# VFC.net
KiCad netlist of a schematic drawn in Altium Designer
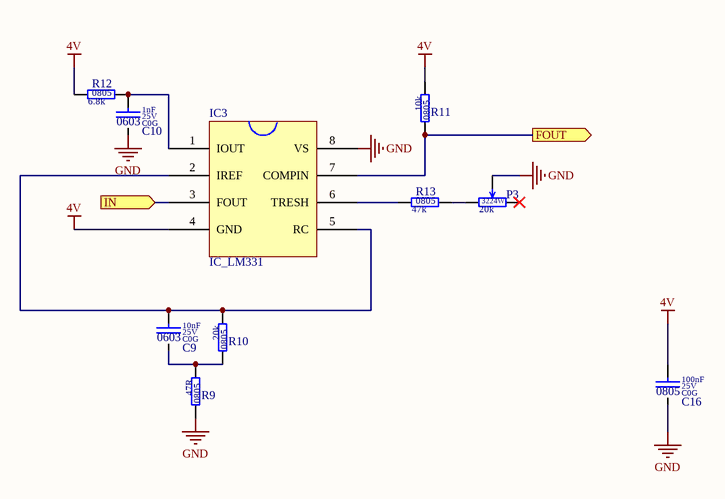
[diagram p0: VFC.SchDoc]

(export (version "E")
  (design (tool "Eeschema 10.0.6"))
  (components
    (comp (ref "C9")
      (value "10nF")
      (footprint "C_0603_1608")
      (description "Capacitor")
      (fields
        (field (name "DIELECTRIC") "C0G")
        (field (name "VOLTAGE") "25V")
        (field (name "SCH_FOOTPRINT") "0603")
        (field (name "Comment") "C_10nF_0603_C0G_25V_5")
      )
      (libsource (lib "SIUE_Symbol") (part "C_10nF_0603_C0G_25V_5"))
    )
    (comp (ref "C10")
      (value "1nF")
      (footprint "C_0603_1608")
      (description "Capacitor")
      (fields
        (field (name "DIELECTRIC") "C0G")
        (field (name "VOLTAGE") "25V")
        (field (name "SCH_FOOTPRINT") "0603")
        (field (name "Comment") "C_1nF_0603_C0G_25V_5")
      )
      (libsource (lib "SIUE_Symbol") (part "C_1nF_0603_C0G_25V_5"))
    )
    (comp (ref "C16")
      (value "100nF")
      (footprint "C_0805_2012")
      (description "Capacitor")
      (fields
        (field (name "DIELECTRIC") "C0G")
        (field (name "VOLTAGE") "25V")
        (field (name "SCH_FOOTPRINT") "0805")
        (field (name "Comment") "C_100nF_0805_C0G_25V_5")
      )
      (libsource (lib "SIUE_Symbol") (part "C_100nF_0805_C0G_25V_5"))
    )
    (comp (ref "IC3") (value "IC_LM331") (footprint "DIP8") (libsource (lib "SIUE_Symbol") (part "IC_LM331")))
    (comp (ref "P3")
      (value "20k")
      (footprint "Potentiometer")
      (fields (field (name "SCH_FOOTPRINT") "3224W") (field (name "Comment") "POT"))
      (libsource (lib "SIUE_Symbol") (part "POT"))
    )
    (comp (ref "R9")
      (value "R_47R_0805_5")
      (footprint "R_0805_2012")
      (fields
        (field (name "TOLERANCE") "5")
        (field (name "SCH_FOOTPRINT") "0805")
        (field (name "RESISTANCE") "47R")
      )
      (libsource (lib "SIUE_Symbol") (part "R_47R_0805_5"))
    )
    (comp (ref "R10")
      (value "R_22k_0805_5")
      (footprint "R_0805_2012")
      (fields
        (field (name "TOLERANCE") "5")
        (field (name "SCH_FOOTPRINT") "0805")
        (field (name "RESISTANCE") "20k")
      )
      (libsource (lib "SIUE_Symbol") (part "R_22k_0805_5"))
    )
    (comp (ref "R11")
      (value "R_10k_0805_5")
      (footprint "R_0805_2012")
      (fields
        (field (name "TOLERANCE") "5")
        (field (name "SCH_FOOTPRINT") "0805")
        (field (name "RESISTANCE") "10k")
      )
      (libsource (lib "SIUE_Symbol") (part "R_10k_0805_5"))
    )
    (comp (ref "R12")
      (value "R_6.8k_0805_5")
      (footprint "R_0805_2012")
      (fields
        (field (name "TOLERANCE") "5")
        (field (name "SCH_FOOTPRINT") "0805")
        (field (name "RESISTANCE") "6.8k")
      )
      (libsource (lib "SIUE_Symbol") (part "R_6.8k_0805_5"))
    )
    (comp (ref "R13")
      (value "R_47k_0805_5")
      (footprint "R_0805_2012")
      (fields
        (field (name "TOLERANCE") "5")
        (field (name "SCH_FOOTPRINT") "0805")
        (field (name "RESISTANCE") "47k")
      )
      (libsource (lib "SIUE_Symbol") (part "R_47k_0805_5"))
    )
  )
  (nets
    (net (code "1") (name "/FOUT") (class "Default")
      (node (ref "IC3") (pin "7") (pinfunction "COMPIN_7") (pintype "passive"))
      (node (ref "R11") (pin "2") (pinfunction "2_2") (pintype "passive"))
    )
    (net (code "2") (name "/IN") (class "Default")
      (node (ref "IC3") (pin "3") (pinfunction "FOUT_3") (pintype "passive"))
    )
    (net (code "3") (name "4V") (class "Default")
      (node (ref "C16") (pin "1") (pinfunction "1_1") (pintype "passive"))
      (node (ref "IC3") (pin "4") (pinfunction "GND_4") (pintype "passive"))
      (node (ref "R11") (pin "1") (pinfunction "1_1") (pintype "passive"))
      (node (ref "R12") (pin "1") (pinfunction "1_1") (pintype "passive"))
    )
    (net (code "4") (name "GND") (class "Default")
      (node (ref "C10") (pin "2") (pinfunction "2_2") (pintype "passive"))
      (node (ref "C16") (pin "2") (pinfunction "2_2") (pintype "passive"))
      (node (ref "IC3") (pin "8") (pinfunction "VS_8") (pintype "passive"))
      (node (ref "P3") (pin "2") (pinfunction "2_2") (pintype "passive"))
      (node (ref "R9") (pin "2") (pinfunction "2_2") (pintype "passive"))
    )
    (net (code "5") (name "Net-(C9-Pad2)") (class "Default")
      (node (ref "C9") (pin "2") (pinfunction "2_2") (pintype "passive"))
      (node (ref "R10") (pin "2") (pinfunction "2_2") (pintype "passive"))
      (node (ref "R9") (pin "1") (pinfunction "1_1") (pintype "passive"))
    )
    (net (code "6") (name "Net-(IC3-IOUT)") (class "Default")
      (node (ref "C10") (pin "1") (pinfunction "1_1") (pintype "passive"))
      (node (ref "IC3") (pin "1") (pinfunction "IOUT_1") (pintype "passive"))
      (node (ref "R12") (pin "2") (pinfunction "2_2") (pintype "passive"))
    )
    (net (code "7") (name "Net-(IC3-IREF)") (class "Default")
      (node (ref "C9") (pin "1") (pinfunction "1_1") (pintype "passive"))
      (node (ref "IC3") (pin "2") (pinfunction "IREF_2") (pintype "passive"))
      (node (ref "IC3") (pin "5") (pinfunction "RC_5") (pintype "passive"))
      (node (ref "R10") (pin "1") (pinfunction "1_1") (pintype "passive"))
    )
    (net (code "8") (name "Net-(IC3-TRESH)") (class "Default")
      (node (ref "IC3") (pin "6") (pinfunction "TRESH_6") (pintype "passive"))
      (node (ref "R13") (pin "1") (pinfunction "1_1") (pintype "passive"))
    )
    (net (code "9") (name "Net-(P3-Pad1)") (class "Default")
      (node (ref "P3") (pin "1") (pinfunction "1_1") (pintype "passive"))
      (node (ref "R13") (pin "2") (pinfunction "2_2") (pintype "passive"))
    )
    (net (code "10") (name "unconnected-(P3-Pad3)") (class "Default")
      (node (ref "P3") (pin "3") (pinfunction "3_3") (pintype "passive+no_connect"))
    )
  )
)
